# HV_Sense.net
KiCad netlist of a schematic drawn in Altium Designer
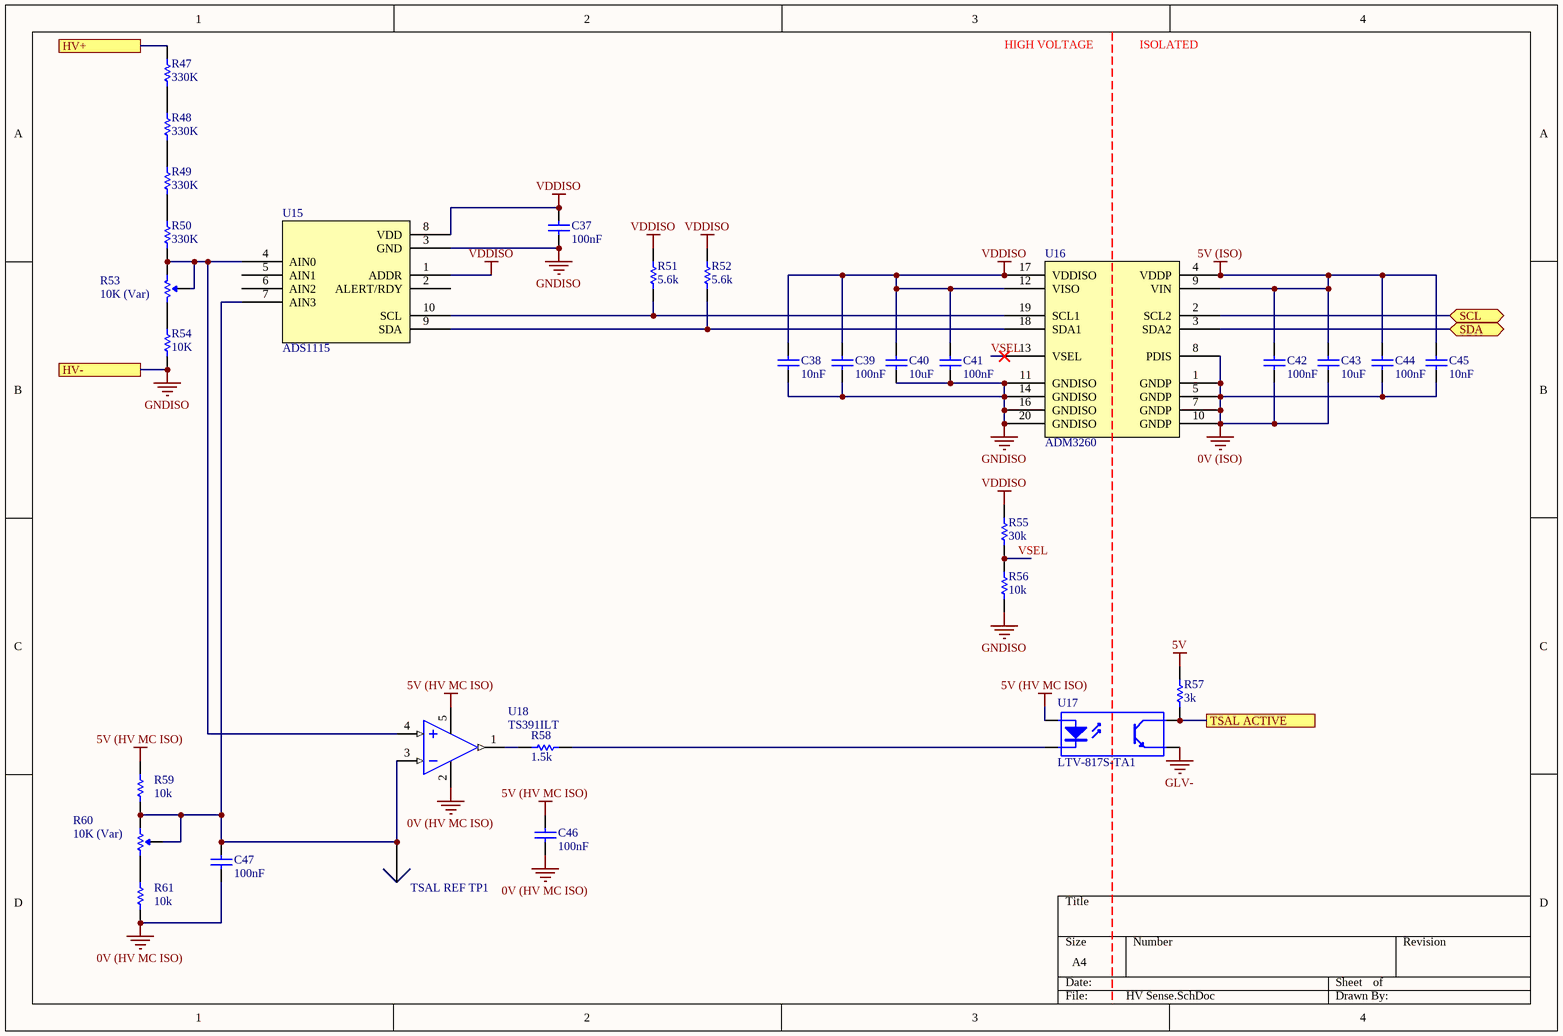
[diagram p0: HV Sense.SchDoc]

(export (version "E")
  (design (tool "Eeschema 10.0.6"))
  (components
    (comp (ref "C37")
      (value "100nF")
      (footprint "0805")
      (fields
        (field (name "PART NUMBER") "GCM21BR71E104KA37L")
        (field (name "TOLERANCE") "10%")
        (field (name "MANUFACTURER") "muRata")
      )
      (libsource (lib "ts_20-standard-library") (part "Capacitor"))
    )
    (comp (ref "C38")
      (value "10nF")
      (footprint "0805")
      (fields
        (field (name "PART NUMBER") "GCM21BR71H103KA37L")
        (field (name "TOLERANCE") "10%")
        (field (name "MANUFACTURER") "muRata")
      )
      (libsource (lib "ts_20-standard-library") (part "Capacitor"))
    )
    (comp (ref "C39")
      (value "100nF")
      (footprint "0805")
      (fields
        (field (name "PART NUMBER") "GCM21BR71E104KA37L")
        (field (name "TOLERANCE") "10%")
        (field (name "MANUFACTURER") "muRata")
      )
      (libsource (lib "ts_20-standard-library") (part "Capacitor"))
    )
    (comp (ref "C40")
      (value "10uF")
      (footprint "0805")
      (fields
        (field (name "PART NUMBER") "GRM21BR6YA106KE43L")
        (field (name "TOLERANCE") "10%")
        (field (name "MANUFACTURER") "muRata")
      )
      (libsource (lib "ts_20-standard-library") (part "Capacitor"))
    )
    (comp (ref "C41")
      (value "100nF")
      (footprint "0805")
      (fields
        (field (name "PART NUMBER") "GCM21BR71E104KA37L")
        (field (name "TOLERANCE") "10%")
        (field (name "MANUFACTURER") "muRata")
      )
      (libsource (lib "ts_20-standard-library") (part "Capacitor"))
    )
    (comp (ref "C42")
      (value "100nF")
      (footprint "0805")
      (fields
        (field (name "PART NUMBER") "GCM21BR71E104KA37L")
        (field (name "TOLERANCE") "10%")
        (field (name "MANUFACTURER") "muRata")
      )
      (libsource (lib "ts_20-standard-library") (part "Capacitor"))
    )
    (comp (ref "C43")
      (value "10uF")
      (footprint "0805")
      (fields
        (field (name "PART NUMBER") "GRM21BR6YA106KE43L")
        (field (name "TOLERANCE") "10%")
        (field (name "MANUFACTURER") "muRata")
      )
      (libsource (lib "ts_20-standard-library") (part "Capacitor"))
    )
    (comp (ref "C44")
      (value "100nF")
      (footprint "0805")
      (fields
        (field (name "PART NUMBER") "GCM21BR71E104KA37L")
        (field (name "TOLERANCE") "10%")
        (field (name "MANUFACTURER") "muRata")
      )
      (libsource (lib "ts_20-standard-library") (part "Capacitor"))
    )
    (comp (ref "C45")
      (value "10nF")
      (footprint "0805")
      (fields
        (field (name "PART NUMBER") "GCM21BR71H103KA37L")
        (field (name "TOLERANCE") "10%")
        (field (name "MANUFACTURER") "muRata")
      )
      (libsource (lib "ts_20-standard-library") (part "Capacitor"))
    )
    (comp (ref "C46")
      (value "100nF")
      (footprint "0805")
      (fields
        (field (name "PART NUMBER") "GCM21BR71E104KA37L")
        (field (name "TOLERANCE") "10%")
        (field (name "MANUFACTURER") "muRata")
      )
      (libsource (lib "ts_20-standard-library") (part "Capacitor"))
    )
    (comp (ref "C47")
      (value "100nF")
      (footprint "0805")
      (fields
        (field (name "PART NUMBER") "GCM21BR71E104KA37L")
        (field (name "TOLERANCE") "10%")
        (field (name "MANUFACTURER") "muRata")
      )
      (libsource (lib "ts_20-standard-library") (part "Capacitor"))
    )
    (comp (ref "R47")
      (value "330K")
      (footprint "VB 0204")
      (fields
        (field (name "PART NUMBER") "MMA02040C3303FB300")
        (field (name "MANUFACTURER") "Vishay Beyschlag")
        (field (name "TOLERANCE") "0.01")
      )
      (libsource (lib "ts_20-standard-library") (part "Resistor"))
    )
    (comp (ref "R48")
      (value "330K")
      (footprint "VB 0204")
      (fields
        (field (name "PART NUMBER") "MMA02040C3303FB300")
        (field (name "MANUFACTURER") "Vishay Beyschlag")
        (field (name "TOLERANCE") "0.01")
      )
      (libsource (lib "ts_20-standard-library") (part "Resistor"))
    )
    (comp (ref "R49")
      (value "330K")
      (footprint "VB 0204")
      (fields
        (field (name "PART NUMBER") "MMA02040C3303FB300")
        (field (name "MANUFACTURER") "Vishay Beyschlag")
        (field (name "TOLERANCE") "0.01")
      )
      (libsource (lib "ts_20-standard-library") (part "Resistor"))
    )
    (comp (ref "R50")
      (value "330K")
      (footprint "VB 0204")
      (fields
        (field (name "PART NUMBER") "MMA02040C3303FB300")
        (field (name "MANUFACTURER") "Vishay Beyschlag")
        (field (name "TOLERANCE") "0.01")
      )
      (libsource (lib "ts_20-standard-library") (part "Resistor"))
    )
    (comp (ref "R51")
      (value "5.6k")
      (footprint "0805")
      (fields
        (field (name "PART NUMBER") "RC0805FR075K6L")
        (field (name "MANUFACTURER") "YAGEO")
        (field (name "TOLERANCE") "0.01")
      )
      (libsource (lib "ts_20-standard-library") (part "Resistor"))
    )
    (comp (ref "R52")
      (value "5.6k")
      (footprint "0805")
      (fields
        (field (name "PART NUMBER") "RC0805FR075K6L")
        (field (name "MANUFACTURER") "YAGEO")
        (field (name "TOLERANCE") "0.01")
      )
      (libsource (lib "ts_20-standard-library") (part "Resistor"))
    )
    (comp (ref "R53")
      (value "10K (Var)")
      (footprint "B 3296")
      (fields
        (field (name "PART NUMBER") "3296W-1-103LF")
        (field (name "MANUFACTURER") "Bournes Inc")
        (field (name "TOLERANCE") "0.1")
      )
      (libsource (lib "ts_20-standard-library") (part "Resistor (Potentiometer)"))
    )
    (comp (ref "R54")
      (value "10K")
      (footprint "VB 0204")
      (fields
        (field (name "PART NUMBER") "MMA02040C1002FB300")
        (field (name "MANUFACTURER") "Vishay Beyschlag")
        (field (name "TOLERANCE") "0.01")
      )
      (libsource (lib "ts_20-standard-library") (part "Resistor"))
    )
    (comp (ref "R55")
      (value "30k")
      (footprint "0805")
      (fields
        (field (name "PART NUMBER") "RC0805FR0730KL")
        (field (name "MANUFACTURER") "YAGEO")
        (field (name "TOLERANCE") "0.01")
      )
      (libsource (lib "ts_20-standard-library") (part "Resistor"))
    )
    (comp (ref "R56")
      (value "10k")
      (footprint "0805")
      (fields
        (field (name "PART NUMBER") "RC0805FR0710KL")
        (field (name "MANUFACTURER") "YAGEO")
        (field (name "TOLERANCE") "0.01")
      )
      (libsource (lib "ts_20-standard-library") (part "Resistor"))
    )
    (comp (ref "R57")
      (value "3k")
      (footprint "0805")
      (fields
        (field (name "PART NUMBER") "RC0805FR073KL")
        (field (name "MANUFACTURER") "YAGEO")
        (field (name "TOLERANCE") "0.01")
      )
      (libsource (lib "ts_20-standard-library") (part "Resistor"))
    )
    (comp (ref "R58")
      (value "1.5k")
      (footprint "0805")
      (fields
        (field (name "PART NUMBER") "RC0805FR071K5L")
        (field (name "MANUFACTURER") "YAGEO")
        (field (name "TOLERANCE") "0.01")
      )
      (libsource (lib "ts_20-standard-library") (part "Resistor"))
    )
    (comp (ref "R59")
      (value "10k")
      (footprint "0805")
      (fields
        (field (name "PART NUMBER") "RC0805FR0710KL")
        (field (name "MANUFACTURER") "YAGEO")
        (field (name "TOLERANCE") "0.01")
      )
      (libsource (lib "ts_20-standard-library") (part "Resistor"))
    )
    (comp (ref "R60")
      (value "10K (Var)")
      (footprint "B 3296")
      (fields
        (field (name "PART NUMBER") "3296W-1-103LF")
        (field (name "MANUFACTURER") "Bournes Inc")
        (field (name "TOLERANCE") "0.1")
      )
      (libsource (lib "ts_20-standard-library") (part "Resistor (Potentiometer)"))
    )
    (comp (ref "R61")
      (value "10k")
      (footprint "0805")
      (fields
        (field (name "PART NUMBER") "RC0805FR0710KL")
        (field (name "MANUFACTURER") "YAGEO")
        (field (name "TOLERANCE") "0.01")
      )
      (libsource (lib "ts_20-standard-library") (part "Resistor"))
    )
    (comp (ref "TSAL REF TP1")
      (value "0mm")
      (footprint "TH Test Point")
      (fields (field (name "PART NUMBER") "TH Test Point") (field (name "CONTACT") "NA"))
      (libsource (lib "ts_20-standard-connectors") (part "Test Point"))
    )
    (comp (ref "U15")
      (value "ADS1115")
      (footprint "TI 10-VSSOP")
      (description "16 Bit Analog to Digital Converter 2, 4 Input 1 Sigma-Delta 10-VSSOP")
      (fields
        (field (name "MANUFACTURER") "Texas Instruments")
        (field (name "DIGIKEY PART NUMBER") "296-38849-1-ND")
      )
      (libsource (lib "ts_20-standard-library") (part "ADS1115"))
    )
    (comp (ref "U16")
      (value "ADM3260")
      (footprint "AD 20-SSOP")
      (description "I²C Digital Isolator 2500Vrms 2 Channel 25kV/µs CMTI 20-SSOP (0.209\", 5.30mm Width)")
      (fields
        (field (name "MANUFACTURER") "Analog Devices")
        (field (name "DIGIKEY PART NUMBER") "ADM3260ARSZ-RL7CT-ND")
      )
      (libsource (lib "ts_20-standard-library") (part "ADM3260"))
    )
    (comp (ref "U17")
      (value "LTV-817S-TA1")
      (footprint "ON 4-SMD")
      (description "35V 50ma Optocoupler (VF=1.2V)")
      (fields
        (field (name "MANUFACTURER") "Lite-On Inc")
        (field (name "DIGIKEY PART NUMBER") "160-1893-2-ND")
      )
      (libsource (lib "ts_20-standard-library") (part "LTV-817S-TA1"))
    )
    (comp (ref "U18")
      (value "TS391ILT")
      (footprint "ON SOT-23-5")
      (description "IC COMP LO PWR SGL V SOT 23-5L")
      (fields
        (field (name "MANUFACTURER") "STMicroelectronics")
        (field (name "DIGIKEY PART NUMBER") "497-2275-2-ND")
      )
      (libsource (lib "ts_20-standard-library") (part "TS391ILT"))
    )
  )
  (nets
    (net (code "1") (name "/HV+") (class "Default")
      (node (ref "R47") (pin "2") (pinfunction "2_2") (pintype "passive"))
    )
    (net (code "2") (name "/SCL") (class "Default")
      (node (ref "U16") (pin "2") (pinfunction "SCL2_2") (pintype "passive"))
    )
    (net (code "3") (name "/SDA") (class "Default")
      (node (ref "U16") (pin "3") (pinfunction "SDA2_3") (pintype "passive"))
    )
    (net (code "4") (name "/TSAL ACTIVE") (class "Default")
      (node (ref "R57") (pin "1") (pinfunction "1_1") (pintype "passive"))
      (node (ref "U17") (pin "4") (pinfunction "C_4") (pintype "passive"))
    )
    (net (code "5") (name "/VSEL") (class "Default")
      (node (ref "R55") (pin "1") (pinfunction "1_1") (pintype "passive"))
      (node (ref "R56") (pin "2") (pinfunction "2_2") (pintype "passive"))
      (node (ref "U16") (pin "13") (pinfunction "VSEL_13") (pintype "passive"))
    )
    (net (code "6") (name "0V (HV MC ISO)") (class "Default")
      (node (ref "C46") (pin "1") (pinfunction "1_1") (pintype "passive"))
      (node (ref "C47") (pin "1") (pinfunction "1_1") (pintype "passive"))
      (node (ref "R61") (pin "1") (pinfunction "1_1") (pintype "passive"))
      (node (ref "U18") (pin "2") (pinfunction "VCC-_2") (pintype "power_in"))
    )
    (net (code "7") (name "0V (ISO)") (class "Default")
      (node (ref "C42") (pin "1") (pinfunction "1_1") (pintype "passive"))
      (node (ref "C43") (pin "1") (pinfunction "1_1") (pintype "passive"))
      (node (ref "C44") (pin "1") (pinfunction "1_1") (pintype "passive"))
      (node (ref "C45") (pin "1") (pinfunction "1_1") (pintype "passive"))
      (node (ref "U16") (pin "1") (pinfunction "GNDP_1") (pintype "passive"))
      (node (ref "U16") (pin "10") (pinfunction "GNDP_10") (pintype "passive"))
      (node (ref "U16") (pin "5") (pinfunction "GNDP_5") (pintype "passive"))
      (node (ref "U16") (pin "7") (pinfunction "GNDP_7") (pintype "passive"))
      (node (ref "U16") (pin "8") (pinfunction "PDIS_8") (pintype "passive"))
    )
    (net (code "8") (name "5V") (class "Default")
      (node (ref "R57") (pin "2") (pinfunction "2_2") (pintype "passive"))
    )
    (net (code "9") (name "5V (HV MC ISO)") (class "Default")
      (node (ref "C46") (pin "2") (pinfunction "2_2") (pintype "passive"))
      (node (ref "R59") (pin "2") (pinfunction "2_2") (pintype "passive"))
      (node (ref "U17") (pin "1") (pinfunction "A_1") (pintype "passive"))
      (node (ref "U18") (pin "5") (pinfunction "VCC+_5") (pintype "power_in"))
    )
    (net (code "10") (name "5V (ISO)") (class "Default")
      (node (ref "C42") (pin "2") (pinfunction "2_2") (pintype "passive"))
      (node (ref "C43") (pin "2") (pinfunction "2_2") (pintype "passive"))
      (node (ref "C44") (pin "2") (pinfunction "2_2") (pintype "passive"))
      (node (ref "C45") (pin "2") (pinfunction "2_2") (pintype "passive"))
      (node (ref "U16") (pin "4") (pinfunction "VDDP_4") (pintype "passive"))
      (node (ref "U16") (pin "9") (pinfunction "VIN_9") (pintype "passive"))
    )
    (net (code "11") (name "GLV-") (class "Default")
      (node (ref "U17") (pin "3") (pinfunction "E_3") (pintype "passive"))
    )
    (net (code "12") (name "GNDISO") (class "Default")
      (node (ref "C37") (pin "2") (pinfunction "2_2") (pintype "passive"))
      (node (ref "C38") (pin "1") (pinfunction "1_1") (pintype "passive"))
      (node (ref "C39") (pin "1") (pinfunction "1_1") (pintype "passive"))
      (node (ref "C40") (pin "1") (pinfunction "1_1") (pintype "passive"))
      (node (ref "C41") (pin "2") (pinfunction "2_2") (pintype "passive"))
      (node (ref "R54") (pin "1") (pinfunction "1_1") (pintype "passive"))
      (node (ref "R56") (pin "1") (pinfunction "1_1") (pintype "passive"))
      (node (ref "U15") (pin "3") (pinfunction "GND_3") (pintype "passive"))
      (node (ref "U16") (pin "11") (pinfunction "GNDISO_11") (pintype "passive"))
      (node (ref "U16") (pin "14") (pinfunction "GNDISO_14") (pintype "passive"))
      (node (ref "U16") (pin "16") (pinfunction "GNDISO_16") (pintype "passive"))
      (node (ref "U16") (pin "20") (pinfunction "GNDISO_20") (pintype "passive"))
    )
    (net (code "13") (name "Net-(R47-Pad1)") (class "Default")
      (node (ref "R47") (pin "1") (pinfunction "1_1") (pintype "passive"))
      (node (ref "R48") (pin "2") (pinfunction "2_2") (pintype "passive"))
    )
    (net (code "14") (name "Net-(R48-Pad1)") (class "Default")
      (node (ref "R48") (pin "1") (pinfunction "1_1") (pintype "passive"))
      (node (ref "R49") (pin "2") (pinfunction "2_2") (pintype "passive"))
    )
    (net (code "15") (name "Net-(R49-Pad1)") (class "Default")
      (node (ref "R49") (pin "1") (pinfunction "1_1") (pintype "passive"))
      (node (ref "R50") (pin "2") (pinfunction "2_2") (pintype "passive"))
    )
    (net (code "16") (name "Net-(R53-CCW)") (class "Default")
      (node (ref "R53") (pin "1") (pinfunction "CCW_1") (pintype "passive"))
      (node (ref "R54") (pin "2") (pinfunction "2_2") (pintype "passive"))
    )
    (net (code "17") (name "Net-(R53-CW)") (class "Default")
      (node (ref "R50") (pin "1") (pinfunction "1_1") (pintype "passive"))
      (node (ref "R53") (pin "2") (pinfunction "Wiper_2") (pintype "passive"))
      (node (ref "R53") (pin "3") (pinfunction "CW_3") (pintype "passive"))
      (node (ref "U15") (pin "4") (pinfunction "AIN0_4") (pintype "passive"))
      (node (ref "U18") (pin "4") (pinfunction "IIN+_4") (pintype "input"))
    )
    (net (code "18") (name "Net-(R60-CCW)") (class "Default")
      (node (ref "C47") (pin "2") (pinfunction "2_2") (pintype "passive"))
      (node (ref "R59") (pin "1") (pinfunction "1_1") (pintype "passive"))
      (node (ref "R60") (pin "1") (pinfunction "CCW_1") (pintype "passive"))
      (node (ref "R60") (pin "2") (pinfunction "Wiper_2") (pintype "passive"))
      (node (ref "TSAL REF TP1") (pin "1") (pinfunction "1_1") (pintype "passive"))
      (node (ref "U15") (pin "7") (pinfunction "AIN3_7") (pintype "passive"))
      (node (ref "U18") (pin "3") (pinfunction "IN-_3") (pintype "input"))
    )
    (net (code "19") (name "Net-(R60-CW)") (class "Default")
      (node (ref "R60") (pin "3") (pinfunction "CW_3") (pintype "passive"))
      (node (ref "R61") (pin "2") (pinfunction "2_2") (pintype "passive"))
    )
    (net (code "20") (name "Net-(U15-SCL)") (class "Default")
      (node (ref "R51") (pin "1") (pinfunction "1_1") (pintype "passive"))
      (node (ref "U15") (pin "10") (pinfunction "SCL_10") (pintype "passive"))
      (node (ref "U16") (pin "19") (pinfunction "SCL1_19") (pintype "passive"))
    )
    (net (code "21") (name "Net-(U15-SDA)") (class "Default")
      (node (ref "R52") (pin "1") (pinfunction "1_1") (pintype "passive"))
      (node (ref "U15") (pin "9") (pinfunction "SDA_9") (pintype "passive"))
      (node (ref "U16") (pin "18") (pinfunction "SDA1_18") (pintype "passive"))
    )
    (net (code "22") (name "Net-(U17-K)") (class "Default")
      (node (ref "R58") (pin "2") (pinfunction "2_2") (pintype "passive"))
      (node (ref "U17") (pin "2") (pinfunction "K_2") (pintype "passive"))
    )
    (net (code "23") (name "Net-(U18-OUT)") (class "Default")
      (node (ref "R58") (pin "1") (pinfunction "1_1") (pintype "passive"))
      (node (ref "U18") (pin "1") (pinfunction "OUT_1") (pintype "output"))
    )
    (net (code "24") (name "VDDISO") (class "Default")
      (node (ref "C37") (pin "1") (pinfunction "1_1") (pintype "passive"))
      (node (ref "C38") (pin "2") (pinfunction "2_2") (pintype "passive"))
      (node (ref "C39") (pin "2") (pinfunction "2_2") (pintype "passive"))
      (node (ref "C40") (pin "2") (pinfunction "2_2") (pintype "passive"))
      (node (ref "C41") (pin "1") (pinfunction "1_1") (pintype "passive"))
      (node (ref "R51") (pin "2") (pinfunction "2_2") (pintype "passive"))
      (node (ref "R52") (pin "2") (pinfunction "2_2") (pintype "passive"))
      (node (ref "R55") (pin "2") (pinfunction "2_2") (pintype "passive"))
      (node (ref "U15") (pin "1") (pinfunction "ADDR_1") (pintype "passive"))
      (node (ref "U15") (pin "8") (pinfunction "VDD_8") (pintype "passive"))
      (node (ref "U16") (pin "12") (pinfunction "VISO_12") (pintype "passive"))
      (node (ref "U16") (pin "17") (pinfunction "VDDISO_17") (pintype "passive"))
    )
    (net (code "25") (name "unconnected-(U15-AIN1-Pad5)") (class "Default")
      (node (ref "U15") (pin "5") (pinfunction "AIN1_5") (pintype "passive"))
    )
    (net (code "26") (name "unconnected-(U15-AIN2-Pad6)") (class "Default")
      (node (ref "U15") (pin "6") (pinfunction "AIN2_6") (pintype "passive"))
    )
    (net (code "27") (name "unconnected-(U15-ALERT{slash}RDY-Pad2)") (class "Default")
      (node (ref "U15") (pin "2") (pinfunction "ALERT/RDY_2") (pintype "passive"))
    )
  )
)
